# EncoderTBPCB.net
KiCad netlist of a schematic drawn in EAGLE
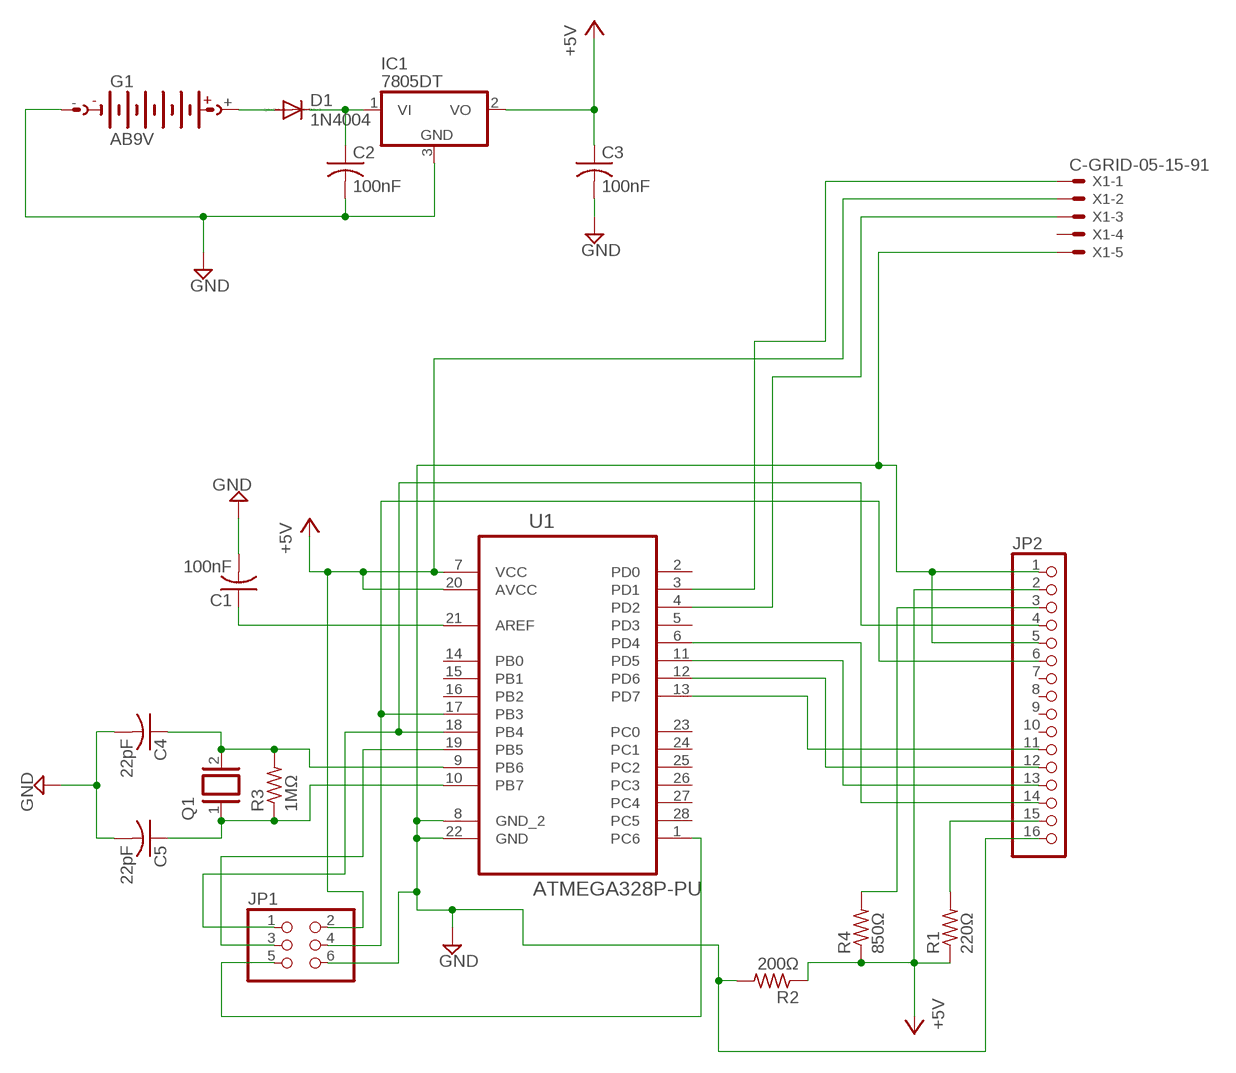
[diagram p0: schematic, sheet 1]

(export (version "E")
  (design (tool "Eeschema 10.0.6"))
  (components
    (comp (ref "C1")
      (value "100nF")
      (footprint "eagle-import:C0603")
      (libsource (lib "eagle-import") (part "C-USC0603"))
    )
    (comp (ref "C2")
      (value "100nF")
      (footprint "eagle-import:C0603")
      (libsource (lib "eagle-import") (part "C-USC0603"))
    )
    (comp (ref "C3")
      (value "100nF")
      (footprint "eagle-import:C0603")
      (libsource (lib "eagle-import") (part "C-USC0603"))
    )
    (comp (ref "C4")
      (value "22pF")
      (footprint "eagle-import:C0603")
      (libsource (lib "eagle-import") (part "C-USC0603"))
    )
    (comp (ref "C5")
      (value "22pF")
      (footprint "eagle-import:C0603")
      (libsource (lib "eagle-import") (part "C-USC0603"))
    )
    (comp (ref "D1")
      (value "1N4004")
      (footprint "eagle-import:DO41-10")
      (libsource (lib "eagle-import") (part "1N4004"))
    )
    (comp (ref "G1")
      (value "AB9V")
      (footprint "eagle-import:AB9V")
      (libsource (lib "eagle-import") (part "AB9V"))
    )
    (comp (ref "IC1")
      (value "7805DT")
      (footprint "eagle-import:TO252")
      (libsource (lib "eagle-import") (part "78DT05"))
    )
    (comp (ref "JP1")
      (value "PINHD-2X3")
      (footprint "eagle-import:2X03")
      (libsource (lib "eagle-import") (part "PINHD-2X3"))
    )
    (comp (ref "JP2")
      (value "PINHD-1X16")
      (footprint "eagle-import:1X16")
      (libsource (lib "eagle-import") (part "PINHD-1X16"))
    )
    (comp (ref "Q1")
      (value "XTAL/S")
      (footprint "eagle-import:QS")
      (libsource (lib "eagle-import") (part "XTAL/S"))
    )
    (comp (ref "R1")
      (value "220Ω")
      (footprint "eagle-import:R0603")
      (libsource (lib "eagle-import") (part "R-US_R0603"))
    )
    (comp (ref "R2")
      (value "200Ω")
      (footprint "eagle-import:R0603")
      (libsource (lib "eagle-import") (part "R-US_R0603"))
    )
    (comp (ref "R3")
      (value "1MΩ")
      (footprint "eagle-import:R0603")
      (libsource (lib "eagle-import") (part "R-US_R0603"))
    )
    (comp (ref "R4")
      (value "850Ω")
      (footprint "eagle-import:R0603")
      (libsource (lib "eagle-import") (part "R-US_R0603"))
    )
    (comp (ref "U1")
      (value "ATMEGA328P-PU")
      (footprint "eagle-import:DIP254P762X457-28")
      (libsource (lib "eagle-import") (part "ATMEGA328P-PU"))
    )
    (comp (ref "X1")
      (value "C-GRID-05-15-91")
      (footprint "eagle-import:15-91-05")
      (libsource (lib "eagle-import") (part "C-GRID-05-15-91"))
    )
  )
  (nets
    (net (code "1") (name "+5V") (class "Default")
      (node (ref "C3") (pin "1") (pinfunction "1_1") (pintype "passive"))
      (node (ref "IC1") (pin "2") (pinfunction "VO_2") (pintype "passive"))
      (node (ref "JP1") (pin "2") (pinfunction "2_2") (pintype "passive"))
      (node (ref "JP2") (pin "2") (pinfunction "2_2") (pintype "passive"))
      (node (ref "R1") (pin "1") (pinfunction "1_1") (pintype "passive"))
      (node (ref "R2") (pin "1") (pinfunction "1_1") (pintype "passive"))
      (node (ref "R4") (pin "1") (pinfunction "1_1") (pintype "passive"))
      (node (ref "U1") (pin "20") (pinfunction "AVCC_20") (pintype "power_in"))
      (node (ref "U1") (pin "7") (pinfunction "VCC_7") (pintype "power_in"))
      (node (ref "X1") (pin "2") (pinfunction "S_2") (pintype "passive"))
    )
    (net (code "2") (name "GND") (class "Default")
      (node (ref "C1") (pin "2") (pinfunction "2_2") (pintype "passive"))
      (node (ref "C2") (pin "2") (pinfunction "2_2") (pintype "passive"))
      (node (ref "C3") (pin "2") (pinfunction "2_2") (pintype "passive"))
      (node (ref "C4") (pin "2") (pinfunction "2_2") (pintype "passive"))
      (node (ref "C5") (pin "2") (pinfunction "2_2") (pintype "passive"))
      (node (ref "G1") (pin "-") (pinfunction "-_-") (pintype "passive"))
      (node (ref "IC1") (pin "3") (pinfunction "GND_3") (pintype "passive"))
      (node (ref "JP1") (pin "6") (pinfunction "6_6") (pintype "passive"))
      (node (ref "JP2") (pin "1") (pinfunction "1_1") (pintype "passive"))
      (node (ref "JP2") (pin "16") (pinfunction "16_16") (pintype "passive"))
      (node (ref "JP2") (pin "5") (pinfunction "5_5") (pintype "passive"))
      (node (ref "R2") (pin "2") (pinfunction "2_2") (pintype "passive"))
      (node (ref "U1") (pin "22") (pinfunction "GND_22") (pintype "passive"))
      (node (ref "U1") (pin "8") (pinfunction "GND_2_8") (pintype "passive"))
      (node (ref "X1") (pin "5") (pinfunction "S_5") (pintype "passive"))
    )
    (net (code "3") (name "Net-(D1-PadA)") (class "Default")
      (node (ref "D1") (pin "A") (pinfunction "A_A") (pintype "passive"))
      (node (ref "G1") (pin "+") (pinfunction "+_+") (pintype "passive"))
    )
    (net (code "4") (name "Net-(IC1-VI)") (class "Default")
      (node (ref "C2") (pin "1") (pinfunction "1_1") (pintype "passive"))
      (node (ref "D1") (pin "C") (pinfunction "C_C") (pintype "passive"))
      (node (ref "IC1") (pin "1") (pinfunction "VI_1") (pintype "input"))
    )
    (net (code "5") (name "Net-(JP2-Pad3)") (class "Default")
      (node (ref "JP2") (pin "3") (pinfunction "3_3") (pintype "passive"))
      (node (ref "R4") (pin "2") (pinfunction "2_2") (pintype "passive"))
    )
    (net (code "6") (name "Net-(JP2-Pad15)") (class "Default")
      (node (ref "JP2") (pin "15") (pinfunction "15_15") (pintype "passive"))
      (node (ref "R1") (pin "2") (pinfunction "2_2") (pintype "passive"))
    )
    (net (code "7") (name "Net-(U1-AREF)") (class "Default")
      (node (ref "C1") (pin "1") (pinfunction "1_1") (pintype "passive"))
      (node (ref "U1") (pin "21") (pinfunction "AREF_21") (pintype "input"))
    )
    (net (code "8") (name "Net-(U1-PB3)") (class "Default")
      (node (ref "JP1") (pin "4") (pinfunction "4_4") (pintype "passive"))
      (node (ref "JP2") (pin "6") (pinfunction "6_6") (pintype "passive"))
      (node (ref "U1") (pin "17") (pinfunction "PB3_17") (pintype "bidirectional"))
    )
    (net (code "9") (name "Net-(U1-PB4)") (class "Default")
      (node (ref "JP1") (pin "1") (pinfunction "1_1") (pintype "passive"))
      (node (ref "JP2") (pin "4") (pinfunction "4_4") (pintype "passive"))
      (node (ref "U1") (pin "18") (pinfunction "PB4_18") (pintype "bidirectional"))
    )
    (net (code "10") (name "Net-(U1-PB5)") (class "Default")
      (node (ref "JP1") (pin "3") (pinfunction "3_3") (pintype "passive"))
      (node (ref "U1") (pin "19") (pinfunction "PB5_19") (pintype "bidirectional"))
    )
    (net (code "11") (name "Net-(U1-PB6)") (class "Default")
      (node (ref "C4") (pin "1") (pinfunction "1_1") (pintype "passive"))
      (node (ref "Q1") (pin "2") (pinfunction "2_2") (pintype "passive"))
      (node (ref "R3") (pin "2") (pinfunction "2_2") (pintype "passive"))
      (node (ref "U1") (pin "9") (pinfunction "PB6_9") (pintype "bidirectional"))
    )
    (net (code "12") (name "Net-(U1-PB7)") (class "Default")
      (node (ref "C5") (pin "1") (pinfunction "1_1") (pintype "passive"))
      (node (ref "Q1") (pin "1") (pinfunction "1_1") (pintype "passive"))
      (node (ref "R3") (pin "1") (pinfunction "1_1") (pintype "passive"))
      (node (ref "U1") (pin "10") (pinfunction "PB7_10") (pintype "bidirectional"))
    )
    (net (code "13") (name "Net-(U1-PC6)") (class "Default")
      (node (ref "JP1") (pin "5") (pinfunction "5_5") (pintype "passive"))
      (node (ref "U1") (pin "1") (pinfunction "PC6_1") (pintype "bidirectional"))
    )
    (net (code "14") (name "Net-(U1-PD1)") (class "Default")
      (node (ref "U1") (pin "3") (pinfunction "PD1_3") (pintype "bidirectional"))
      (node (ref "X1") (pin "1") (pinfunction "S_1") (pintype "passive"))
    )
    (net (code "15") (name "Net-(U1-PD2)") (class "Default")
      (node (ref "U1") (pin "4") (pinfunction "PD2_4") (pintype "bidirectional"))
      (node (ref "X1") (pin "3") (pinfunction "S_3") (pintype "passive"))
    )
    (net (code "16") (name "Net-(U1-PD4)") (class "Default")
      (node (ref "JP2") (pin "14") (pinfunction "14_14") (pintype "passive"))
      (node (ref "U1") (pin "6") (pinfunction "PD4_6") (pintype "bidirectional"))
    )
    (net (code "17") (name "Net-(U1-PD5)") (class "Default")
      (node (ref "JP2") (pin "13") (pinfunction "13_13") (pintype "passive"))
      (node (ref "U1") (pin "11") (pinfunction "PD5_11") (pintype "bidirectional"))
    )
    (net (code "18") (name "Net-(U1-PD6)") (class "Default")
      (node (ref "JP2") (pin "12") (pinfunction "12_12") (pintype "passive"))
      (node (ref "U1") (pin "12") (pinfunction "PD6_12") (pintype "bidirectional"))
    )
    (net (code "19") (name "Net-(U1-PD7)") (class "Default")
      (node (ref "JP2") (pin "11") (pinfunction "11_11") (pintype "passive"))
      (node (ref "U1") (pin "13") (pinfunction "PD7_13") (pintype "bidirectional"))
    )
    (net (code "20") (name "unconnected-(JP2-Pad7)") (class "Default")
      (node (ref "JP2") (pin "7") (pinfunction "7_7") (pintype "passive"))
    )
    (net (code "21") (name "unconnected-(JP2-Pad8)") (class "Default")
      (node (ref "JP2") (pin "8") (pinfunction "8_8") (pintype "passive"))
    )
    (net (code "22") (name "unconnected-(JP2-Pad9)") (class "Default")
      (node (ref "JP2") (pin "9") (pinfunction "9_9") (pintype "passive"))
    )
    (net (code "23") (name "unconnected-(JP2-Pad10)") (class "Default")
      (node (ref "JP2") (pin "10") (pinfunction "10_10") (pintype "passive"))
    )
    (net (code "24") (name "unconnected-(U1-PB0-Pad14)") (class "Default")
      (node (ref "U1") (pin "14") (pinfunction "PB0_14") (pintype "bidirectional"))
    )
    (net (code "25") (name "unconnected-(U1-PB1-Pad15)") (class "Default")
      (node (ref "U1") (pin "15") (pinfunction "PB1_15") (pintype "bidirectional"))
    )
    (net (code "26") (name "unconnected-(U1-PB2-Pad16)") (class "Default")
      (node (ref "U1") (pin "16") (pinfunction "PB2_16") (pintype "bidirectional"))
    )
    (net (code "27") (name "unconnected-(U1-PC0-Pad23)") (class "Default")
      (node (ref "U1") (pin "23") (pinfunction "PC0_23") (pintype "bidirectional"))
    )
    (net (code "28") (name "unconnected-(U1-PC1-Pad24)") (class "Default")
      (node (ref "U1") (pin "24") (pinfunction "PC1_24") (pintype "bidirectional"))
    )
    (net (code "29") (name "unconnected-(U1-PC2-Pad25)") (class "Default")
      (node (ref "U1") (pin "25") (pinfunction "PC2_25") (pintype "bidirectional"))
    )
    (net (code "30") (name "unconnected-(U1-PC3-Pad26)") (class "Default")
      (node (ref "U1") (pin "26") (pinfunction "PC3_26") (pintype "bidirectional"))
    )
    (net (code "31") (name "unconnected-(U1-PC4-Pad27)") (class "Default")
      (node (ref "U1") (pin "27") (pinfunction "PC4_27") (pintype "bidirectional"))
    )
    (net (code "32") (name "unconnected-(U1-PC5-Pad28)") (class "Default")
      (node (ref "U1") (pin "28") (pinfunction "PC5_28") (pintype "bidirectional"))
    )
    (net (code "33") (name "unconnected-(U1-PD0-Pad2)") (class "Default")
      (node (ref "U1") (pin "2") (pinfunction "PD0_2") (pintype "bidirectional"))
    )
    (net (code "34") (name "unconnected-(U1-PD3-Pad5)") (class "Default")
      (node (ref "U1") (pin "5") (pinfunction "PD3_5") (pintype "bidirectional"))
    )
    (net (code "35") (name "unconnected-(X1D-S-Pad4)") (class "Default")
      (node (ref "X1") (pin "4") (pinfunction "S_4") (pintype "passive"))
    )
  )
)
